# SiPM_Smart_Probe.net
KiCad netlist of a schematic drawn in Altium Designer
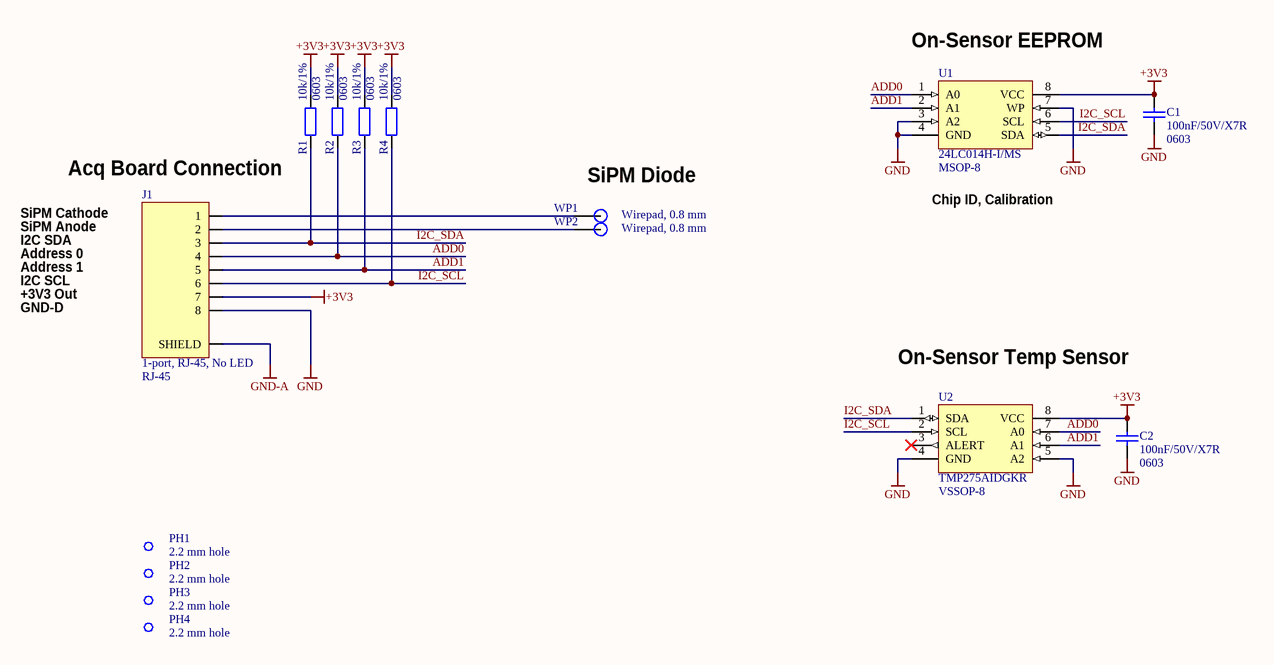
[diagram p0: SiPM_Smart_Probe.SchDoc]

(export (version "E")
  (design (tool "Eeschema 10.0.6"))
  (components
    (comp (ref "C1")
      (value "100nF/50V/X7R")
      (footprint "sm_cap_0603")
      (description "MLCC capacitor, non-polarized")
      (fields
        (field (name "MANUFACTURER") "Yageo")
        (field (name "PART NUMBER") "CC0603KRX7R9BB104")
        (field (name "PACKAGE") "0603")
      )
      (libsource (lib "RICE_local") (part "Capacitor_0603_100n_50V_X7R"))
    )
    (comp (ref "C2")
      (value "100nF/50V/X7R")
      (footprint "sm_cap_0603")
      (description "MLCC capacitor, non-polarized")
      (fields
        (field (name "MANUFACTURER") "Yageo")
        (field (name "PART NUMBER") "CC0603KRX7R9BB104")
        (field (name "PACKAGE") "0603")
      )
      (libsource (lib "RICE_local") (part "Capacitor_0603_100n_50V_X7R"))
    )
    (comp (ref "J1")
      (value "1-port, RJ-45, No LED")
      (footprint "RJ45_1_PORT_NOLED")
      (fields
        (field (name "MANUFACTURER") "Amphenol")
        (field (name "PART NUMBER") "RJSBE5380C1")
        (field (name "PACKAGE") "RJ-45")
      )
      (libsource (lib "Library_KEI_Ruzicka") (part "RJ45_1_PORT_NOLED"))
    )
    (comp (ref "PH1")
      (value "2.2 mm hole")
      (footprint "c480h220")
      (libsource (lib "Library_KEI_Ruzicka") (part "PLATED_HOLE2.2_PAD4.8"))
    )
    (comp (ref "PH2")
      (value "2.2 mm hole")
      (footprint "c480h220")
      (libsource (lib "Library_KEI_Ruzicka") (part "PLATED_HOLE2.2_PAD4.8"))
    )
    (comp (ref "PH3")
      (value "2.2 mm hole")
      (footprint "c480h220")
      (libsource (lib "Library_KEI_Ruzicka") (part "PLATED_HOLE2.2_PAD4.8"))
    )
    (comp (ref "PH4")
      (value "2.2 mm hole")
      (footprint "c480h220")
      (libsource (lib "Library_KEI_Ruzicka") (part "PLATED_HOLE2.2_PAD4.8"))
    )
    (comp (ref "R1")
      (value "10k/1%")
      (footprint "sm_res_0603")
      (description "Chip resistor")
      (fields
        (field (name "MANUFACTURER") "Yageo")
        (field (name "PART NUMBER") "RC0603FR-0710KL")
        (field (name "PACKAGE") "0603")
      )
      (libsource (lib "RICE_local") (part "Resistor_0603_10k_1%"))
    )
    (comp (ref "R2")
      (value "10k/1%")
      (footprint "sm_res_0603")
      (description "Chip resistor")
      (fields
        (field (name "MANUFACTURER") "Yageo")
        (field (name "PART NUMBER") "RC0603FR-0710KL")
        (field (name "PACKAGE") "0603")
      )
      (libsource (lib "RICE_local") (part "Resistor_0603_10k_1%"))
    )
    (comp (ref "R3")
      (value "10k/1%")
      (footprint "sm_res_0603")
      (description "Chip resistor")
      (fields
        (field (name "MANUFACTURER") "Yageo")
        (field (name "PART NUMBER") "RC0603FR-0710KL")
        (field (name "PACKAGE") "0603")
      )
      (libsource (lib "RICE_local") (part "Resistor_0603_10k_1%"))
    )
    (comp (ref "R4")
      (value "10k/1%")
      (footprint "sm_res_0603")
      (description "Chip resistor")
      (fields
        (field (name "MANUFACTURER") "Yageo")
        (field (name "PART NUMBER") "RC0603FR-0710KL")
        (field (name "PACKAGE") "0603")
      )
      (libsource (lib "RICE_local") (part "Resistor_0603_10k_1%"))
    )
    (comp (ref "U1")
      (value "24LC014H-I/MS")
      (footprint "MSOP-8")
      (description "I2C EEPROM 1K 128x8")
      (fields (field (name "MANUFACTURER") "Microchip Technology") (field (name "PACKAGE") "MSOP-8"))
      (libsource (lib "Library_KEI_Ruzicka") (part "24LC014H-I/MS"))
    )
    (comp (ref "U2")
      (value "TMP275AIDGKR")
      (footprint "VSSOP-8")
      (description "I2C ±0.5°C Temperature Sensor")
      (fields (field (name "MANUFACTURER") "Texas Instruments") (field (name "PACKAGE") "VSSOP-8"))
      (libsource (lib "Library_KEI_Ruzicka") (part "TMP275"))
    )
    (comp (ref "WP1")
      (value "Wirepad, 0.8 mm")
      (footprint "Wirepad_0.8MM")
      (libsource (lib "RICE_local") (part "Wirepad_0.8MM"))
    )
    (comp (ref "WP2")
      (value "Wirepad, 0.8 mm")
      (footprint "Wirepad_0.8MM")
      (libsource (lib "RICE_local") (part "Wirepad_0.8MM"))
    )
  )
  (nets
    (net (code "1") (name "+3V3") (class "Default")
      (node (ref "C1") (pin "2") (pinfunction "2_2") (pintype "passive"))
      (node (ref "C2") (pin "2") (pinfunction "2_2") (pintype "passive"))
      (node (ref "J1") (pin "7") (pinfunction "7_7") (pintype "passive"))
      (node (ref "R1") (pin "2") (pinfunction "2_2") (pintype "passive"))
      (node (ref "R2") (pin "2") (pinfunction "2_2") (pintype "passive"))
      (node (ref "R3") (pin "2") (pinfunction "2_2") (pintype "passive"))
      (node (ref "R4") (pin "2") (pinfunction "2_2") (pintype "passive"))
      (node (ref "U1") (pin "8") (pinfunction "VCC_8") (pintype "passive"))
      (node (ref "U2") (pin "8") (pinfunction "VCC_8") (pintype "passive"))
    )
    (net (code "2") (name "/ADD0") (class "Default")
      (node (ref "J1") (pin "4") (pinfunction "4_4") (pintype "passive"))
      (node (ref "R2") (pin "1") (pinfunction "1_1") (pintype "passive"))
      (node (ref "U1") (pin "1") (pinfunction "A0_1") (pintype "input"))
      (node (ref "U2") (pin "7") (pinfunction "A0_7") (pintype "input"))
    )
    (net (code "3") (name "/ADD1") (class "Default")
      (node (ref "J1") (pin "5") (pinfunction "5_5") (pintype "passive"))
      (node (ref "R3") (pin "1") (pinfunction "1_1") (pintype "passive"))
      (node (ref "U1") (pin "2") (pinfunction "A1_2") (pintype "input"))
      (node (ref "U2") (pin "6") (pinfunction "A1_6") (pintype "input"))
    )
    (net (code "4") (name "/I2C_SCL") (class "Default")
      (node (ref "J1") (pin "6") (pinfunction "6_6") (pintype "passive"))
      (node (ref "R4") (pin "1") (pinfunction "1_1") (pintype "passive"))
      (node (ref "U1") (pin "6") (pinfunction "SCL_6") (pintype "input"))
      (node (ref "U2") (pin "2") (pinfunction "SCL_2") (pintype "input"))
    )
    (net (code "5") (name "/I2C_SDA") (class "Default")
      (node (ref "J1") (pin "3") (pinfunction "3_3") (pintype "passive"))
      (node (ref "R1") (pin "1") (pinfunction "1_1") (pintype "passive"))
      (node (ref "U1") (pin "5") (pinfunction "SDA_5") (pintype "bidirectional"))
      (node (ref "U2") (pin "1") (pinfunction "SDA_1") (pintype "bidirectional"))
    )
    (net (code "6") (name "GND") (class "Default")
      (node (ref "C1") (pin "1") (pinfunction "1_1") (pintype "passive"))
      (node (ref "C2") (pin "1") (pinfunction "1_1") (pintype "passive"))
      (node (ref "J1") (pin "8") (pinfunction "8_8") (pintype "passive"))
      (node (ref "U1") (pin "3") (pinfunction "A2_3") (pintype "input"))
      (node (ref "U1") (pin "4") (pinfunction "GND_4") (pintype "passive"))
      (node (ref "U1") (pin "7") (pinfunction "WP_7") (pintype "input"))
      (node (ref "U2") (pin "4") (pinfunction "GND_4") (pintype "passive"))
      (node (ref "U2") (pin "5") (pinfunction "A2_5") (pintype "input"))
    )
    (net (code "7") (name "GND-A") (class "Default")
      (node (ref "J1") (pin "SHIELD") (pinfunction "SHIELD_SHIELD") (pintype "passive"))
    )
    (net (code "8") (name "Net-(J1-Pad1)") (class "Default")
      (node (ref "J1") (pin "1") (pinfunction "1_1") (pintype "passive"))
      (node (ref "WP1") (pin "1") (pinfunction "1_1") (pintype "passive"))
    )
    (net (code "9") (name "Net-(J1-Pad2)") (class "Default")
      (node (ref "J1") (pin "2") (pinfunction "2_2") (pintype "passive"))
      (node (ref "WP2") (pin "1") (pinfunction "1_1") (pintype "passive"))
    )
    (net (code "10") (name "unconnected-(PH1-Pad1)") (class "Default")
      (node (ref "PH1") (pin "1") (pinfunction "1_1") (pintype "bidirectional"))
    )
    (net (code "11") (name "unconnected-(PH2-Pad1)") (class "Default")
      (node (ref "PH2") (pin "1") (pinfunction "1_1") (pintype "bidirectional"))
    )
    (net (code "12") (name "unconnected-(PH3-Pad1)") (class "Default")
      (node (ref "PH3") (pin "1") (pinfunction "1_1") (pintype "bidirectional"))
    )
    (net (code "13") (name "unconnected-(PH4-Pad1)") (class "Default")
      (node (ref "PH4") (pin "1") (pinfunction "1_1") (pintype "bidirectional"))
    )
    (net (code "14") (name "unconnected-(U2-ALERT-Pad3)") (class "Default")
      (node (ref "U2") (pin "3") (pinfunction "ALERT_3") (pintype "output+no_connect"))
    )
  )
)
